# CAA-NMC-2-panels.net
KiCad netlist of a schematic drawn in EAGLE
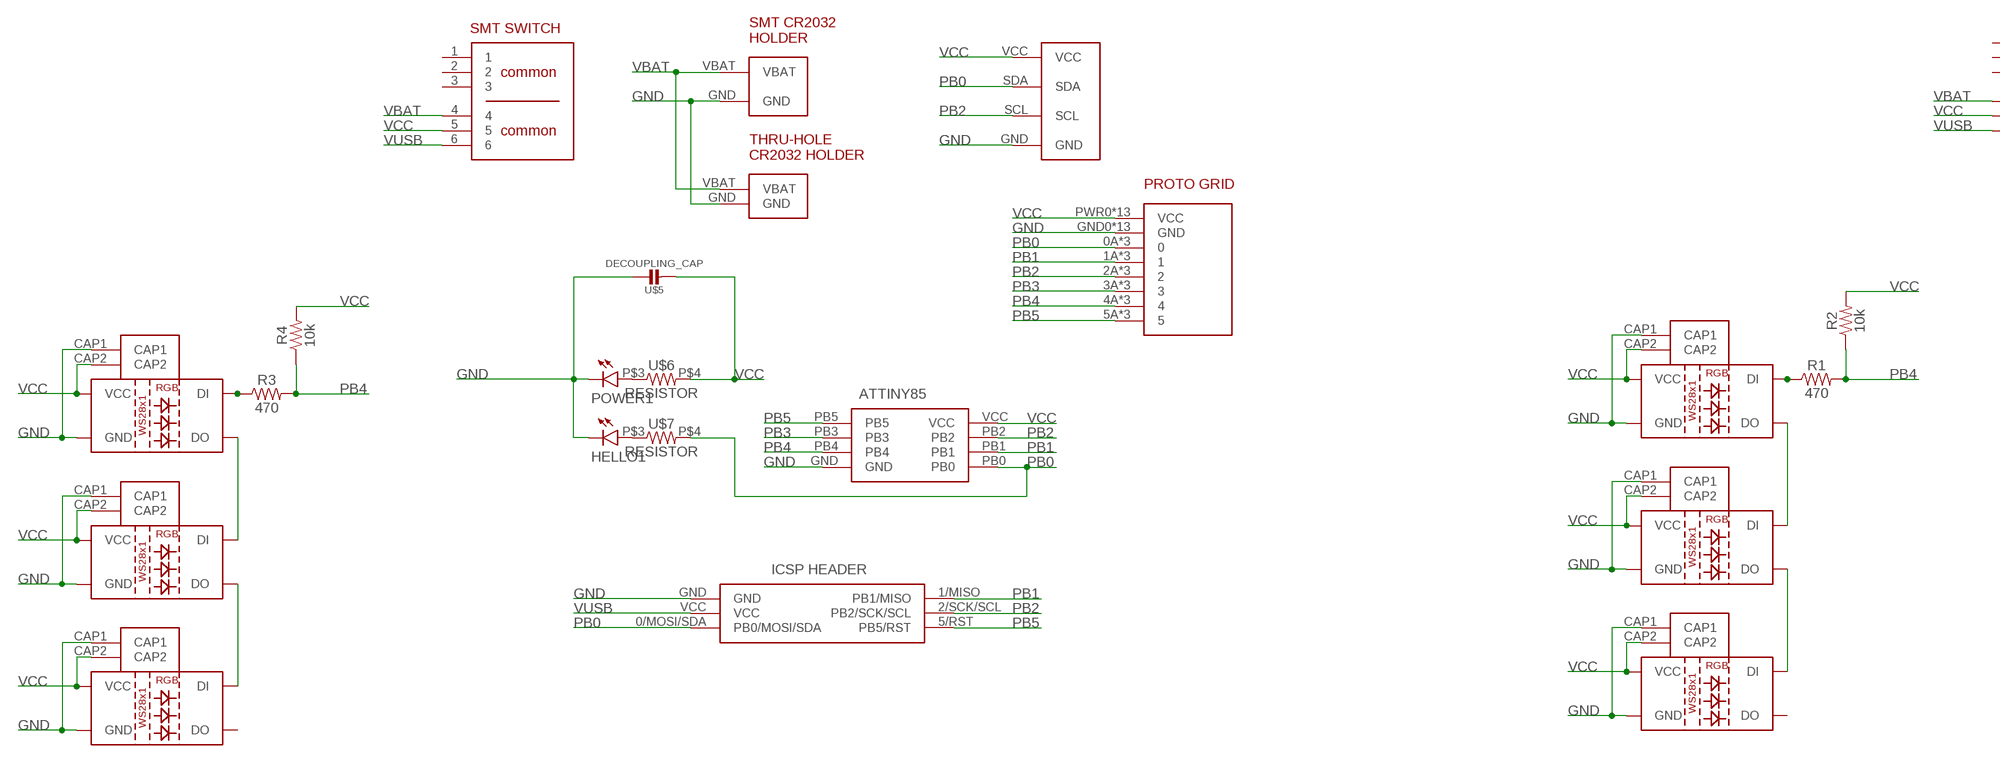
[diagram p0: schematic, sheet 1, part 1 of 2]
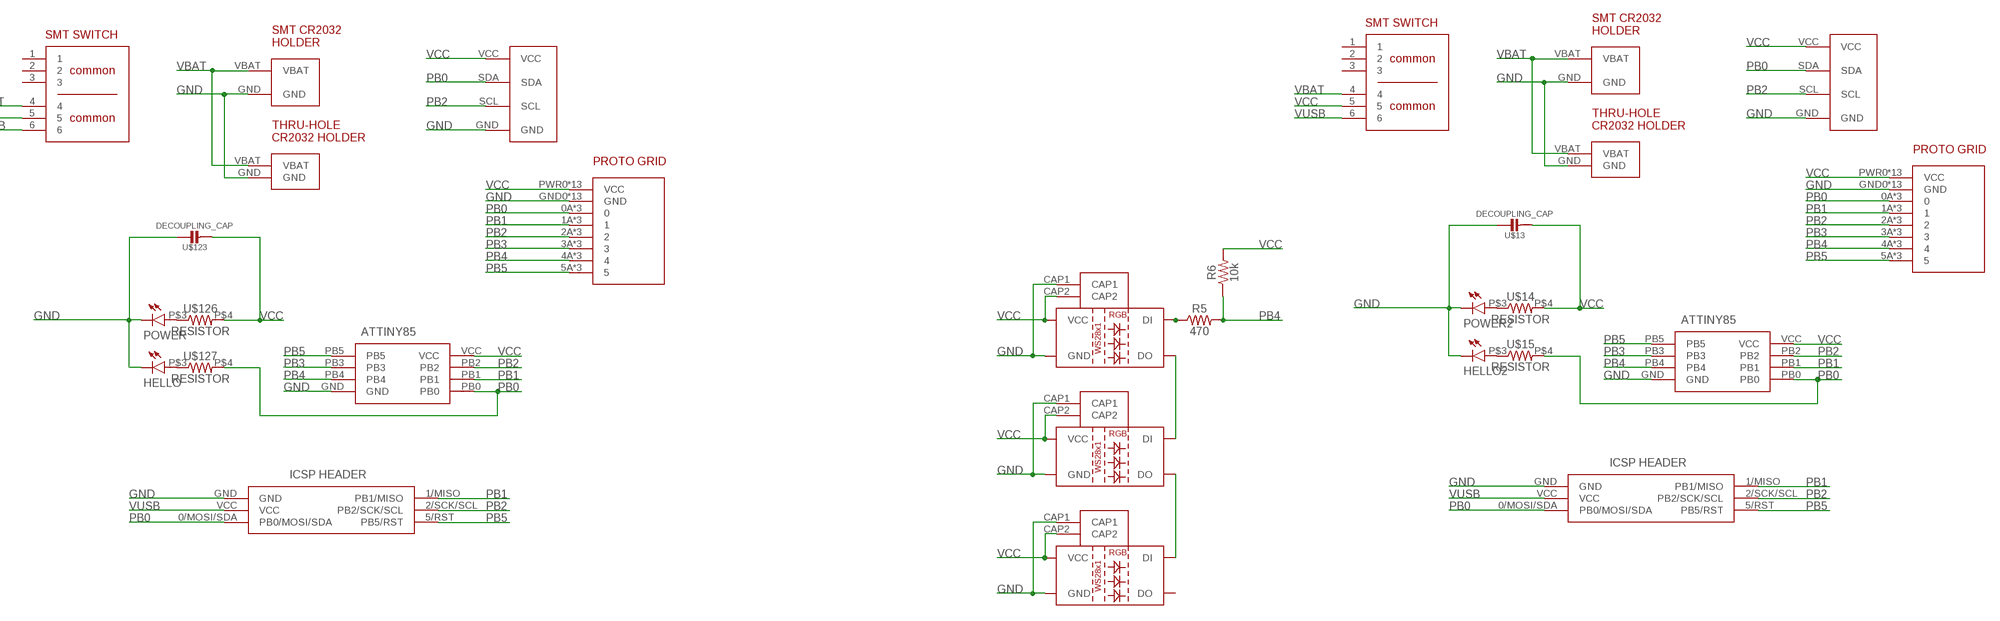
[diagram p1: schematic, sheet 1, part 2 of 2]

(export (version "E")
  (design (tool "Eeschema 10.0.6"))
  (components
    (comp (ref "D1")
      (value "WS2812B")
      (footprint "eagle-import:WS2812B")
      (libsource (lib "eagle-import") (part "WS2812B"))
    )
    (comp (ref "D2")
      (value "WS2812B")
      (footprint "eagle-import:WS2812B")
      (libsource (lib "eagle-import") (part "WS2812B"))
    )
    (comp (ref "D3")
      (value "WS2812B")
      (footprint "eagle-import:WS2812B")
      (libsource (lib "eagle-import") (part "WS2812B"))
    )
    (comp (ref "D4")
      (value "WS2812B")
      (footprint "eagle-import:WS2812B")
      (libsource (lib "eagle-import") (part "WS2812B"))
    )
    (comp (ref "D5")
      (value "WS2812B")
      (footprint "eagle-import:WS2812B")
      (libsource (lib "eagle-import") (part "WS2812B"))
    )
    (comp (ref "D6")
      (value "WS2812B")
      (footprint "eagle-import:WS2812B")
      (libsource (lib "eagle-import") (part "WS2812B"))
    )
    (comp (ref "D7")
      (value "WS2812B")
      (footprint "eagle-import:WS2812B")
      (libsource (lib "eagle-import") (part "WS2812B"))
    )
    (comp (ref "D8")
      (value "WS2812B")
      (footprint "eagle-import:WS2812B")
      (libsource (lib "eagle-import") (part "WS2812B"))
    )
    (comp (ref "D9")
      (value "WS2812B")
      (footprint "eagle-import:WS2812B")
      (libsource (lib "eagle-import") (part "WS2812B"))
    )
    (comp (ref "HELLO")
      (value "LED3MM")
      (footprint "eagle-import:LED3MM")
      (libsource (lib "eagle-import") (part "LED3MM"))
    )
    (comp (ref "HELLO1")
      (value "LED3MM")
      (footprint "eagle-import:LED3MM")
      (libsource (lib "eagle-import") (part "LED3MM"))
    )
    (comp (ref "HELLO2")
      (value "LED3MM")
      (footprint "eagle-import:LED3MM")
      (libsource (lib "eagle-import") (part "LED3MM"))
    )
    (comp (ref "IC1")
      (value "ATTINY85-20SU")
      (footprint "eagle-import:SOT127P798X216-8N")
      (fields (field (name "RS_PART_NUMBER") "1331674"))
      (libsource (lib "eagle-import") (part "ATTINY85-20SU"))
    )
    (comp (ref "IC2")
      (value "ATTINY85-20SU")
      (footprint "eagle-import:SOT127P798X216-8N")
      (fields (field (name "RS_PART_NUMBER") "1331674"))
      (libsource (lib "eagle-import") (part "ATTINY85-20SU"))
    )
    (comp (ref "IC3")
      (value "ATTINY85-20SU")
      (footprint "eagle-import:SOT127P798X216-8N")
      (fields (field (name "RS_PART_NUMBER") "1331674"))
      (libsource (lib "eagle-import") (part "ATTINY85-20SU"))
    )
    (comp (ref "J1")
      (value "M20-9980346")
      (footprint "eagle-import:HDRV6W64P254_2X3_762X508X868P")
      (fields (field (name "RS_PART_NUMBER") "7457046P"))
      (libsource (lib "eagle-import") (part "M20-9980346"))
    )
    (comp (ref "J2")
      (value "M20-9980346")
      (footprint "eagle-import:HDRV6W64P254_2X3_762X508X868P")
      (fields (field (name "RS_PART_NUMBER") "7457046P"))
      (libsource (lib "eagle-import") (part "M20-9980346"))
    )
    (comp (ref "J3")
      (value "M20-9980346")
      (footprint "eagle-import:HDRV6W64P254_2X3_762X508X868P")
      (fields (field (name "RS_PART_NUMBER") "7457046P"))
      (libsource (lib "eagle-import") (part "M20-9980346"))
    )
    (comp (ref "POWER")
      (value "LED3MM")
      (footprint "eagle-import:LED3MM")
      (libsource (lib "eagle-import") (part "LED3MM"))
    )
    (comp (ref "POWER1")
      (value "LED3MM")
      (footprint "eagle-import:LED3MM")
      (libsource (lib "eagle-import") (part "LED3MM"))
    )
    (comp (ref "POWER2")
      (value "LED3MM")
      (footprint "eagle-import:LED3MM")
      (libsource (lib "eagle-import") (part "LED3MM"))
    )
    (comp (ref "R1")
      (value "470")
      (footprint "eagle-import:0603")
      (libsource (lib "eagle-import") (part "470OHM-0603-1/10W-1%"))
    )
    (comp (ref "R2")
      (value "10k")
      (footprint "eagle-import:0603")
      (libsource (lib "eagle-import") (part "10KOHM-0603-1/10W-1%"))
    )
    (comp (ref "R3")
      (value "470")
      (footprint "eagle-import:0603")
      (libsource (lib "eagle-import") (part "470OHM-0603-1/10W-1%"))
    )
    (comp (ref "R4")
      (value "10k")
      (footprint "eagle-import:0603")
      (libsource (lib "eagle-import") (part "10KOHM-0603-1/10W-1%"))
    )
    (comp (ref "R5")
      (value "470")
      (footprint "eagle-import:0603")
      (libsource (lib "eagle-import") (part "470OHM-0603-1/10W-1%"))
    )
    (comp (ref "R6")
      (value "10k")
      (footprint "eagle-import:0603")
      (libsource (lib "eagle-import") (part "10KOHM-0603-1/10W-1%"))
    )
    (comp (ref "U$1")
      (value "PROTO")
      (footprint "eagle-import:PROTO")
      (libsource (lib "eagle-import") (part "PROTO"))
    )
    (comp (ref "U$2")
      (value "SMT-BATTERY-HOLDER")
      (footprint "eagle-import:SMT-CR-HOLDER")
      (libsource (lib "eagle-import") (part "SMT-BATTERY-HOLDER"))
    )
    (comp (ref "U$3")
      (value "THRU-CR-HOLDER")
      (footprint "eagle-import:THRU-CR-HOLDER")
      (libsource (lib "eagle-import") (part "THRU-CR-HOLDER"))
    )
    (comp (ref "U$4")
      (value "I2C-PADS")
      (footprint "eagle-import:I2C-PADS")
      (libsource (lib "eagle-import") (part "I2C-PADS"))
    )
    (comp (ref "U$5")
      (value "DECOUPLING_CAP")
      (footprint "eagle-import:DECOUPLING_CAP")
      (libsource (lib "eagle-import") (part "DECOUPLING_CAP"))
    )
    (comp (ref "U$6")
      (value "RESISTOR")
      (footprint "eagle-import:AXIAL-0.3")
      (libsource (lib "eagle-import") (part "RESISTOR"))
    )
    (comp (ref "U$7")
      (value "RESISTOR")
      (footprint "eagle-import:AXIAL-0.3")
      (libsource (lib "eagle-import") (part "RESISTOR"))
    )
    (comp (ref "U$8")
      (value "SMT-SWITCH")
      (footprint "eagle-import:SMT-SWITCH")
      (libsource (lib "eagle-import") (part "SMT-SWITCH"))
    )
    (comp (ref "U$9")
      (value "PROTO")
      (footprint "eagle-import:PROTO")
      (libsource (lib "eagle-import") (part "PROTO"))
    )
    (comp (ref "U$10")
      (value "SMT-BATTERY-HOLDER")
      (footprint "eagle-import:SMT-CR-HOLDER")
      (libsource (lib "eagle-import") (part "SMT-BATTERY-HOLDER"))
    )
    (comp (ref "U$11")
      (value "THRU-CR-HOLDER")
      (footprint "eagle-import:THRU-CR-HOLDER")
      (libsource (lib "eagle-import") (part "THRU-CR-HOLDER"))
    )
    (comp (ref "U$12")
      (value "I2C-PADS")
      (footprint "eagle-import:I2C-PADS")
      (libsource (lib "eagle-import") (part "I2C-PADS"))
    )
    (comp (ref "U$13")
      (value "DECOUPLING_CAP")
      (footprint "eagle-import:DECOUPLING_CAP")
      (libsource (lib "eagle-import") (part "DECOUPLING_CAP"))
    )
    (comp (ref "U$14")
      (value "RESISTOR")
      (footprint "eagle-import:AXIAL-0.3")
      (libsource (lib "eagle-import") (part "RESISTOR"))
    )
    (comp (ref "U$15")
      (value "RESISTOR")
      (footprint "eagle-import:AXIAL-0.3")
      (libsource (lib "eagle-import") (part "RESISTOR"))
    )
    (comp (ref "U$16")
      (value "SMT-SWITCH")
      (footprint "eagle-import:SMT-SWITCH")
      (libsource (lib "eagle-import") (part "SMT-SWITCH"))
    )
    (comp (ref "U$17")
      (value "PROTO")
      (footprint "eagle-import:PROTO")
      (libsource (lib "eagle-import") (part "PROTO"))
    )
    (comp (ref "U$18")
      (value "SMT-BATTERY-HOLDER")
      (footprint "eagle-import:SMT-CR-HOLDER")
      (libsource (lib "eagle-import") (part "SMT-BATTERY-HOLDER"))
    )
    (comp (ref "U$19")
      (value "THRU-CR-HOLDER")
      (footprint "eagle-import:THRU-CR-HOLDER")
      (libsource (lib "eagle-import") (part "THRU-CR-HOLDER"))
    )
    (comp (ref "U$20")
      (value "I2C-PADS")
      (footprint "eagle-import:I2C-PADS")
      (libsource (lib "eagle-import") (part "I2C-PADS"))
    )
    (comp (ref "U$123")
      (value "DECOUPLING_CAP")
      (footprint "eagle-import:DECOUPLING_CAP")
      (libsource (lib "eagle-import") (part "DECOUPLING_CAP"))
    )
    (comp (ref "U$126")
      (value "RESISTOR")
      (footprint "eagle-import:AXIAL-0.3")
      (libsource (lib "eagle-import") (part "RESISTOR"))
    )
    (comp (ref "U$127")
      (value "RESISTOR")
      (footprint "eagle-import:AXIAL-0.3")
      (libsource (lib "eagle-import") (part "RESISTOR"))
    )
    (comp (ref "U$145")
      (value "SMT-SWITCH")
      (footprint "eagle-import:SMT-SWITCH")
      (libsource (lib "eagle-import") (part "SMT-SWITCH"))
    )
  )
  (nets
    (net (code "1") (name "/GND") (class "Default")
      (node (ref "D1") (pin "CAP1") (pinfunction "CAP1_CAP1") (pintype "bidirectional"))
      (node (ref "D1") (pin "GND") (pinfunction "GND_GND") (pintype "bidirectional"))
      (node (ref "D2") (pin "CAP1") (pinfunction "CAP1_CAP1") (pintype "bidirectional"))
      (node (ref "D2") (pin "GND") (pinfunction "GND_GND") (pintype "bidirectional"))
      (node (ref "D3") (pin "CAP1") (pinfunction "CAP1_CAP1") (pintype "bidirectional"))
      (node (ref "D3") (pin "GND") (pinfunction "GND_GND") (pintype "bidirectional"))
      (node (ref "D4") (pin "CAP1") (pinfunction "CAP1_CAP1") (pintype "bidirectional"))
      (node (ref "D4") (pin "GND") (pinfunction "GND_GND") (pintype "bidirectional"))
      (node (ref "D5") (pin "CAP1") (pinfunction "CAP1_CAP1") (pintype "bidirectional"))
      (node (ref "D5") (pin "GND") (pinfunction "GND_GND") (pintype "bidirectional"))
      (node (ref "D6") (pin "CAP1") (pinfunction "CAP1_CAP1") (pintype "bidirectional"))
      (node (ref "D6") (pin "GND") (pinfunction "GND_GND") (pintype "bidirectional"))
      (node (ref "D7") (pin "CAP1") (pinfunction "CAP1_CAP1") (pintype "bidirectional"))
      (node (ref "D7") (pin "GND") (pinfunction "GND_GND") (pintype "bidirectional"))
      (node (ref "D8") (pin "CAP1") (pinfunction "CAP1_CAP1") (pintype "bidirectional"))
      (node (ref "D8") (pin "GND") (pinfunction "GND_GND") (pintype "bidirectional"))
      (node (ref "D9") (pin "CAP1") (pinfunction "CAP1_CAP1") (pintype "bidirectional"))
      (node (ref "D9") (pin "GND") (pinfunction "GND_GND") (pintype "bidirectional"))
      (node (ref "HELLO") (pin "NEG") (pinfunction "NEG_NEG") (pintype "passive"))
      (node (ref "HELLO1") (pin "NEG") (pinfunction "NEG_NEG") (pintype "passive"))
      (node (ref "HELLO2") (pin "NEG") (pinfunction "NEG_NEG") (pintype "passive"))
      (node (ref "IC1") (pin "GND") (pinfunction "GND_GND") (pintype "bidirectional"))
      (node (ref "IC2") (pin "GND") (pinfunction "GND_GND") (pintype "bidirectional"))
      (node (ref "IC3") (pin "GND") (pinfunction "GND_GND") (pintype "bidirectional"))
      (node (ref "J1") (pin "GND") (pinfunction "GND_GND") (pintype "bidirectional"))
      (node (ref "J2") (pin "GND") (pinfunction "GND_GND") (pintype "bidirectional"))
      (node (ref "J3") (pin "GND") (pinfunction "GND_GND") (pintype "bidirectional"))
      (node (ref "POWER") (pin "NEG") (pinfunction "NEG_NEG") (pintype "passive"))
      (node (ref "POWER1") (pin "NEG") (pinfunction "NEG_NEG") (pintype "passive"))
      (node (ref "POWER2") (pin "NEG") (pinfunction "NEG_NEG") (pintype "passive"))
      (node (ref "U$1") (pin "GND0") (pinfunction "GND_GND0") (pintype "bidirectional"))
      (node (ref "U$1") (pin "GND1") (pinfunction "GND_GND1") (pintype "bidirectional"))
      (node (ref "U$1") (pin "GND10") (pinfunction "GND_GND10") (pintype "bidirectional"))
      (node (ref "U$1") (pin "GND11") (pinfunction "GND_GND11") (pintype "bidirectional"))
      (node (ref "U$1") (pin "GND12") (pinfunction "GND_GND12") (pintype "bidirectional"))
      (node (ref "U$1") (pin "GND2") (pinfunction "GND_GND2") (pintype "bidirectional"))
      (node (ref "U$1") (pin "GND3") (pinfunction "GND_GND3") (pintype "bidirectional"))
      (node (ref "U$1") (pin "GND4") (pinfunction "GND_GND4") (pintype "bidirectional"))
      (node (ref "U$1") (pin "GND5") (pinfunction "GND_GND5") (pintype "bidirectional"))
      (node (ref "U$1") (pin "GND6") (pinfunction "GND_GND6") (pintype "bidirectional"))
      (node (ref "U$1") (pin "GND7") (pinfunction "GND_GND7") (pintype "bidirectional"))
      (node (ref "U$1") (pin "GND8") (pinfunction "GND_GND8") (pintype "bidirectional"))
      (node (ref "U$1") (pin "GND9") (pinfunction "GND_GND9") (pintype "bidirectional"))
      (node (ref "U$10") (pin "GND") (pinfunction "GND_GND") (pintype "bidirectional"))
      (node (ref "U$11") (pin "GND") (pinfunction "GND_GND") (pintype "bidirectional"))
      (node (ref "U$12") (pin "GND") (pinfunction "GND_GND") (pintype "bidirectional"))
      (node (ref "U$123") (pin "P$1") (pinfunction "1_P$1") (pintype "passive"))
      (node (ref "U$13") (pin "P$1") (pinfunction "1_P$1") (pintype "passive"))
      (node (ref "U$17") (pin "GND0") (pinfunction "GND_GND0") (pintype "bidirectional"))
      (node (ref "U$17") (pin "GND1") (pinfunction "GND_GND1") (pintype "bidirectional"))
      (node (ref "U$17") (pin "GND10") (pinfunction "GND_GND10") (pintype "bidirectional"))
      (node (ref "U$17") (pin "GND11") (pinfunction "GND_GND11") (pintype "bidirectional"))
      (node (ref "U$17") (pin "GND12") (pinfunction "GND_GND12") (pintype "bidirectional"))
      (node (ref "U$17") (pin "GND2") (pinfunction "GND_GND2") (pintype "bidirectional"))
      (node (ref "U$17") (pin "GND3") (pinfunction "GND_GND3") (pintype "bidirectional"))
      (node (ref "U$17") (pin "GND4") (pinfunction "GND_GND4") (pintype "bidirectional"))
      (node (ref "U$17") (pin "GND5") (pinfunction "GND_GND5") (pintype "bidirectional"))
      (node (ref "U$17") (pin "GND6") (pinfunction "GND_GND6") (pintype "bidirectional"))
      (node (ref "U$17") (pin "GND7") (pinfunction "GND_GND7") (pintype "bidirectional"))
      (node (ref "U$17") (pin "GND8") (pinfunction "GND_GND8") (pintype "bidirectional"))
      (node (ref "U$17") (pin "GND9") (pinfunction "GND_GND9") (pintype "bidirectional"))
      (node (ref "U$18") (pin "GND") (pinfunction "GND_GND") (pintype "bidirectional"))
      (node (ref "U$19") (pin "GND") (pinfunction "GND_GND") (pintype "bidirectional"))
      (node (ref "U$2") (pin "GND") (pinfunction "GND_GND") (pintype "bidirectional"))
      (node (ref "U$20") (pin "GND") (pinfunction "GND_GND") (pintype "bidirectional"))
      (node (ref "U$3") (pin "GND") (pinfunction "GND_GND") (pintype "bidirectional"))
      (node (ref "U$4") (pin "GND") (pinfunction "GND_GND") (pintype "bidirectional"))
      (node (ref "U$5") (pin "P$1") (pinfunction "1_P$1") (pintype "passive"))
      (node (ref "U$9") (pin "GND0") (pinfunction "GND_GND0") (pintype "bidirectional"))
      (node (ref "U$9") (pin "GND1") (pinfunction "GND_GND1") (pintype "bidirectional"))
      (node (ref "U$9") (pin "GND10") (pinfunction "GND_GND10") (pintype "bidirectional"))
      (node (ref "U$9") (pin "GND11") (pinfunction "GND_GND11") (pintype "bidirectional"))
      (node (ref "U$9") (pin "GND12") (pinfunction "GND_GND12") (pintype "bidirectional"))
      (node (ref "U$9") (pin "GND2") (pinfunction "GND_GND2") (pintype "bidirectional"))
      (node (ref "U$9") (pin "GND3") (pinfunction "GND_GND3") (pintype "bidirectional"))
      (node (ref "U$9") (pin "GND4") (pinfunction "GND_GND4") (pintype "bidirectional"))
      (node (ref "U$9") (pin "GND5") (pinfunction "GND_GND5") (pintype "bidirectional"))
      (node (ref "U$9") (pin "GND6") (pinfunction "GND_GND6") (pintype "bidirectional"))
      (node (ref "U$9") (pin "GND7") (pinfunction "GND_GND7") (pintype "bidirectional"))
      (node (ref "U$9") (pin "GND8") (pinfunction "GND_GND8") (pintype "bidirectional"))
      (node (ref "U$9") (pin "GND9") (pinfunction "GND_GND9") (pintype "bidirectional"))
    )
    (net (code "2") (name "/PB0") (class "Default")
      (node (ref "IC1") (pin "PB0") (pinfunction "PB0_PB0") (pintype "bidirectional"))
      (node (ref "IC2") (pin "PB0") (pinfunction "PB0_PB0") (pintype "bidirectional"))
      (node (ref "IC3") (pin "PB0") (pinfunction "PB0_PB0") (pintype "bidirectional"))
      (node (ref "J1") (pin "0/MOSI/SDA") (pinfunction "PB0/MOSI/SDA_0/MOSI/SDA") (pintype "bidirectional"))
      (node (ref "J2") (pin "0/MOSI/SDA") (pinfunction "PB0/MOSI/SDA_0/MOSI/SDA") (pintype "bidirectional"))
      (node (ref "J3") (pin "0/MOSI/SDA") (pinfunction "PB0/MOSI/SDA_0/MOSI/SDA") (pintype "bidirectional"))
      (node (ref "U$1") (pin "0A") (pinfunction "0_0A") (pintype "bidirectional"))
      (node (ref "U$1") (pin "0B") (pinfunction "0_0B") (pintype "bidirectional"))
      (node (ref "U$1") (pin "0C") (pinfunction "0_0C") (pintype "bidirectional"))
      (node (ref "U$12") (pin "SDA") (pinfunction "SDA_SDA") (pintype "bidirectional"))
      (node (ref "U$127") (pin "P$4") (pinfunction "2_P$4") (pintype "passive"))
      (node (ref "U$15") (pin "P$4") (pinfunction "2_P$4") (pintype "passive"))
      (node (ref "U$17") (pin "0A") (pinfunction "0_0A") (pintype "bidirectional"))
      (node (ref "U$17") (pin "0B") (pinfunction "0_0B") (pintype "bidirectional"))
      (node (ref "U$17") (pin "0C") (pinfunction "0_0C") (pintype "bidirectional"))
      (node (ref "U$20") (pin "SDA") (pinfunction "SDA_SDA") (pintype "bidirectional"))
      (node (ref "U$4") (pin "SDA") (pinfunction "SDA_SDA") (pintype "bidirectional"))
      (node (ref "U$7") (pin "P$4") (pinfunction "2_P$4") (pintype "passive"))
      (node (ref "U$9") (pin "0A") (pinfunction "0_0A") (pintype "bidirectional"))
      (node (ref "U$9") (pin "0B") (pinfunction "0_0B") (pintype "bidirectional"))
      (node (ref "U$9") (pin "0C") (pinfunction "0_0C") (pintype "bidirectional"))
    )
    (net (code "3") (name "/PB1") (class "Default")
      (node (ref "IC1") (pin "PB1") (pinfunction "PB1_PB1") (pintype "bidirectional"))
      (node (ref "IC2") (pin "PB1") (pinfunction "PB1_PB1") (pintype "bidirectional"))
      (node (ref "IC3") (pin "PB1") (pinfunction "PB1_PB1") (pintype "bidirectional"))
      (node (ref "J1") (pin "1/MISO") (pinfunction "PB1/MISO_1/MISO") (pintype "bidirectional"))
      (node (ref "J2") (pin "1/MISO") (pinfunction "PB1/MISO_1/MISO") (pintype "bidirectional"))
      (node (ref "J3") (pin "1/MISO") (pinfunction "PB1/MISO_1/MISO") (pintype "bidirectional"))
      (node (ref "U$1") (pin "1A") (pinfunction "1_1A") (pintype "bidirectional"))
      (node (ref "U$1") (pin "1B") (pinfunction "1_1B") (pintype "bidirectional"))
      (node (ref "U$1") (pin "1C") (pinfunction "1_1C") (pintype "bidirectional"))
      (node (ref "U$17") (pin "1A") (pinfunction "1_1A") (pintype "bidirectional"))
      (node (ref "U$17") (pin "1B") (pinfunction "1_1B") (pintype "bidirectional"))
      (node (ref "U$17") (pin "1C") (pinfunction "1_1C") (pintype "bidirectional"))
      (node (ref "U$9") (pin "1A") (pinfunction "1_1A") (pintype "bidirectional"))
      (node (ref "U$9") (pin "1B") (pinfunction "1_1B") (pintype "bidirectional"))
      (node (ref "U$9") (pin "1C") (pinfunction "1_1C") (pintype "bidirectional"))
    )
    (net (code "4") (name "/PB2") (class "Default")
      (node (ref "IC1") (pin "PB2") (pinfunction "PB2_PB2") (pintype "bidirectional"))
      (node (ref "IC2") (pin "PB2") (pinfunction "PB2_PB2") (pintype "bidirectional"))
      (node (ref "IC3") (pin "PB2") (pinfunction "PB2_PB2") (pintype "bidirectional"))
      (node (ref "J1") (pin "2/SCK/SCL") (pinfunction "PB2/SCK/SCL_2/SCK/SCL") (pintype "bidirectional"))
      (node (ref "J2") (pin "2/SCK/SCL") (pinfunction "PB2/SCK/SCL_2/SCK/SCL") (pintype "bidirectional"))
      (node (ref "J3") (pin "2/SCK/SCL") (pinfunction "PB2/SCK/SCL_2/SCK/SCL") (pintype "bidirectional"))
      (node (ref "U$1") (pin "2A") (pinfunction "2_2A") (pintype "bidirectional"))
      (node (ref "U$1") (pin "2B") (pinfunction "2_2B") (pintype "bidirectional"))
      (node (ref "U$1") (pin "2C") (pinfunction "2_2C") (pintype "bidirectional"))
      (node (ref "U$12") (pin "SCL") (pinfunction "SCL_SCL") (pintype "bidirectional"))
      (node (ref "U$17") (pin "2A") (pinfunction "2_2A") (pintype "bidirectional"))
      (node (ref "U$17") (pin "2B") (pinfunction "2_2B") (pintype "bidirectional"))
      (node (ref "U$17") (pin "2C") (pinfunction "2_2C") (pintype "bidirectional"))
      (node (ref "U$20") (pin "SCL") (pinfunction "SCL_SCL") (pintype "bidirectional"))
      (node (ref "U$4") (pin "SCL") (pinfunction "SCL_SCL") (pintype "bidirectional"))
      (node (ref "U$9") (pin "2A") (pinfunction "2_2A") (pintype "bidirectional"))
      (node (ref "U$9") (pin "2B") (pinfunction "2_2B") (pintype "bidirectional"))
      (node (ref "U$9") (pin "2C") (pinfunction "2_2C") (pintype "bidirectional"))
    )
    (net (code "5") (name "/PB3") (class "Default")
      (node (ref "IC1") (pin "PB3") (pinfunction "PB3_PB3") (pintype "bidirectional"))
      (node (ref "IC2") (pin "PB3") (pinfunction "PB3_PB3") (pintype "bidirectional"))
      (node (ref "IC3") (pin "PB3") (pinfunction "PB3_PB3") (pintype "bidirectional"))
      (node (ref "U$1") (pin "3A") (pinfunction "3_3A") (pintype "bidirectional"))
      (node (ref "U$1") (pin "3B") (pinfunction "3_3B") (pintype "bidirectional"))
      (node (ref "U$1") (pin "3C") (pinfunction "3_3C") (pintype "bidirectional"))
      (node (ref "U$17") (pin "3A") (pinfunction "3_3A") (pintype "bidirectional"))
      (node (ref "U$17") (pin "3B") (pinfunction "3_3B") (pintype "bidirectional"))
      (node (ref "U$17") (pin "3C") (pinfunction "3_3C") (pintype "bidirectional"))
      (node (ref "U$9") (pin "3A") (pinfunction "3_3A") (pintype "bidirectional"))
      (node (ref "U$9") (pin "3B") (pinfunction "3_3B") (pintype "bidirectional"))
      (node (ref "U$9") (pin "3C") (pinfunction "3_3C") (pintype "bidirectional"))
    )
    (net (code "6") (name "/PB4") (class "Default")
      (node (ref "IC1") (pin "PB4") (pinfunction "PB4_PB4") (pintype "bidirectional"))
      (node (ref "IC2") (pin "PB4") (pinfunction "PB4_PB4") (pintype "bidirectional"))
      (node (ref "IC3") (pin "PB4") (pinfunction "PB4_PB4") (pintype "bidirectional"))
      (node (ref "R1") (pin "2") (pinfunction "2_2") (pintype "passive"))
      (node (ref "R2") (pin "1") (pinfunction "1_1") (pintype "passive"))
      (node (ref "R3") (pin "2") (pinfunction "2_2") (pintype "passive"))
      (node (ref "R4") (pin "1") (pinfunction "1_1") (pintype "passive"))
      (node (ref "R5") (pin "2") (pinfunction "2_2") (pintype "passive"))
      (node (ref "R6") (pin "1") (pinfunction "1_1") (pintype "passive"))
      (node (ref "U$1") (pin "4A") (pinfunction "4_4A") (pintype "bidirectional"))
      (node (ref "U$1") (pin "4B") (pinfunction "4_4B") (pintype "bidirectional"))
      (node (ref "U$1") (pin "4C") (pinfunction "4_4C") (pintype "bidirectional"))
      (node (ref "U$17") (pin "4A") (pinfunction "4_4A") (pintype "bidirectional"))
      (node (ref "U$17") (pin "4B") (pinfunction "4_4B") (pintype "bidirectional"))
      (node (ref "U$17") (pin "4C") (pinfunction "4_4C") (pintype "bidirectional"))
      (node (ref "U$9") (pin "4A") (pinfunction "4_4A") (pintype "bidirectional"))
      (node (ref "U$9") (pin "4B") (pinfunction "4_4B") (pintype "bidirectional"))
      (node (ref "U$9") (pin "4C") (pinfunction "4_4C") (pintype "bidirectional"))
    )
    (net (code "7") (name "/PB5") (class "Default")
      (node (ref "IC1") (pin "PB5") (pinfunction "PB5_PB5") (pintype "bidirectional"))
      (node (ref "IC2") (pin "PB5") (pinfunction "PB5_PB5") (pintype "bidirectional"))
      (node (ref "IC3") (pin "PB5") (pinfunction "PB5_PB5") (pintype "bidirectional"))
      (node (ref "J1") (pin "5/RST") (pinfunction "PB5/RST_5/RST") (pintype "bidirectional"))
      (node (ref "J2") (pin "5/RST") (pinfunction "PB5/RST_5/RST") (pintype "bidirectional"))
      (node (ref "J3") (pin "5/RST") (pinfunction "PB5/RST_5/RST") (pintype "bidirectional"))
      (node (ref "U$1") (pin "5A") (pinfunction "5_5A") (pintype "bidirectional"))
      (node (ref "U$1") (pin "5B") (pinfunction "5_5B") (pintype "bidirectional"))
      (node (ref "U$1") (pin "5C") (pinfunction "5_5C") (pintype "bidirectional"))
      (node (ref "U$17") (pin "5A") (pinfunction "5_5A") (pintype "bidirectional"))
      (node (ref "U$17") (pin "5B") (pinfunction "5_5B") (pintype "bidirectional"))
      (node (ref "U$17") (pin "5C") (pinfunction "5_5C") (pintype "bidirectional"))
      (node (ref "U$9") (pin "5A") (pinfunction "5_5A") (pintype "bidirectional"))
      (node (ref "U$9") (pin "5B") (pinfunction "5_5B") (pintype "bidirectional"))
      (node (ref "U$9") (pin "5C") (pinfunction "5_5C") (pintype "bidirectional"))
    )
    (net (code "8") (name "/VBAT") (class "Default")
      (node (ref "U$10") (pin "VBAT") (pinfunction "VBAT_VBAT") (pintype "bidirectional"))
      (node (ref "U$11") (pin "VBAT") (pinfunction "VBAT_VBAT") (pintype "bidirectional"))
      (node (ref "U$145") (pin "4") (pinfunction "4_4") (pintype "bidirectional"))
      (node (ref "U$16") (pin "4") (pinfunction "4_4") (pintype "bidirectional"))
      (node (ref "U$18") (pin "VBAT") (pinfunction "VBAT_VBAT") (pintype "bidirectional"))
      (node (ref "U$19") (pin "VBAT") (pinfunction "VBAT_VBAT") (pintype "bidirectional"))
      (node (ref "U$2") (pin "VBAT") (pinfunction "VBAT_VBAT") (pintype "bidirectional"))
      (node (ref "U$3") (pin "VBAT") (pinfunction "VBAT_VBAT") (pintype "bidirectional"))
      (node (ref "U$8") (pin "4") (pinfunction "4_4") (pintype "bidirectional"))
    )
    (net (code "9") (name "/VCC") (class "Default")
      (node (ref "D1") (pin "CAP2") (pinfunction "CAP2_CAP2") (pintype "bidirectional"))
      (node (ref "D1") (pin "VCC") (pinfunction "VCC_VCC") (pintype "bidirectional"))
      (node (ref "D2") (pin "CAP2") (pinfunction "CAP2_CAP2") (pintype "bidirectional"))
      (node (ref "D2") (pin "VCC") (pinfunction "VCC_VCC") (pintype "bidirectional"))
      (node (ref "D3") (pin "CAP2") (pinfunction "CAP2_CAP2") (pintype "bidirectional"))
      (node (ref "D3") (pin "VCC") (pinfunction "VCC_VCC") (pintype "bidirectional"))
      (node (ref "D4") (pin "CAP2") (pinfunction "CAP2_CAP2") (pintype "bidirectional"))
      (node (ref "D4") (pin "VCC") (pinfunction "VCC_VCC") (pintype "bidirectional"))
      (node (ref "D5") (pin "CAP2") (pinfunction "CAP2_CAP2") (pintype "bidirectional"))
      (node (ref "D5") (pin "VCC") (pinfunction "VCC_VCC") (pintype "bidirectional"))
      (node (ref "D6") (pin "CAP2") (pinfunction "CAP2_CAP2") (pintype "bidirectional"))
      (node (ref "D6") (pin "VCC") (pinfunction "VCC_VCC") (pintype "bidirectional"))
      (node (ref "D7") (pin "CAP2") (pinfunction "CAP2_CAP2") (pintype "bidirectional"))
      (node (ref "D7") (pin "VCC") (pinfunction "VCC_VCC") (pintype "bidirectional"))
      (node (ref "D8") (pin "CAP2") (pinfunction "CAP2_CAP2") (pintype "bidirectional"))
      (node (ref "D8") (pin "VCC") (pinfunction "VCC_VCC") (pintype "bidirectional"))
      (node (ref "D9") (pin "CAP2") (pinfunction "CAP2_CAP2") (pintype "bidirectional"))
      (node (ref "D9") (pin "VCC") (pinfunction "VCC_VCC") (pintype "bidirectional"))
      (node (ref "IC1") (pin "VCC") (pinfunction "VCC_VCC") (pintype "bidirectional"))
      (node (ref "IC2") (pin "VCC") (pinfunction "VCC_VCC") (pintype "bidirectional"))
      (node (ref "IC3") (pin "VCC") (pinfunction "VCC_VCC") (pintype "bidirectional"))
      (node (ref "R2") (pin "2") (pinfunction "2_2") (pintype "passive"))
      (node (ref "R4") (pin "2") (pinfunction "2_2") (pintype "passive"))
      (node (ref "R6") (pin "2") (pinfunction "2_2") (pintype "passive"))
      (node (ref "U$1") (pin "PWR0") (pinfunction "VCC_PWR0") (pintype "bidirectional"))
      (node (ref "U$1") (pin "PWR1") (pinfunction "VCC_PWR1") (pintype "bidirectional"))
      (node (ref "U$1") (pin "PWR10") (pinfunction "VCC_PWR10") (pintype "bidirectional"))
      (node (ref "U$1") (pin "PWR11") (pinfunction "VCC_PWR11") (pintype "bidirectional"))
      (node (ref "U$1") (pin "PWR12") (pinfunction "VCC_PWR12") (pintype "bidirectional"))
      (node (ref "U$1") (pin "PWR2") (pinfunction "VCC_PWR2") (pintype "bidirectional"))
      (node (ref "U$1") (pin "PWR3") (pinfunction "VCC_PWR3") (pintype "bidirectional"))
      (node (ref "U$1") (pin "PWR4") (pinfunction "VCC_PWR4") (pintype "bidirectional"))
      (node (ref "U$1") (pin "PWR5") (pinfunction "VCC_PWR5") (pintype "bidirectional"))
      (node (ref "U$1") (pin "PWR6") (pinfunction "VCC_PWR6") (pintype "bidirectional"))
      (node (ref "U$1") (pin "PWR7") (pinfunction "VCC_PWR7") (pintype "bidirectional"))
      (node (ref "U$1") (pin "PWR8") (pinfunction "VCC_PWR8") (pintype "bidirectional"))
      (node (ref "U$1") (pin "PWR9") (pinfunction "VCC_PWR9") (pintype "bidirectional"))
      (node (ref "U$12") (pin "VCC") (pinfunction "VCC_VCC") (pintype "bidirectional"))
      (node (ref "U$123") (pin "P$2") (pinfunction "2_P$2") (pintype "passive"))
      (node (ref "U$126") (pin "P$4") (pinfunction "2_P$4") (pintype "passive"))
      (node (ref "U$13") (pin "P$2") (pinfunction "2_P$2") (pintype "passive"))
      (node (ref "U$14") (pin "P$4") (pinfunction "2_P$4") (pintype "passive"))
      (node (ref "U$145") (pin "5") (pinfunction "5_5") (pintype "bidirectional"))
      (node (ref "U$16") (pin "5") (pinfunction "5_5") (pintype "bidirectional"))
      (node (ref "U$17") (pin "PWR0") (pinfunction "VCC_PWR0") (pintype "bidirectional"))
      (node (ref "U$17") (pin "PWR1") (pinfunction "VCC_PWR1") (pintype "bidirectional"))
      (node (ref "U$17") (pin "PWR10") (pinfunction "VCC_PWR10") (pintype "bidirectional"))
      (node (ref "U$17") (pin "PWR11") (pinfunction "VCC_PWR11") (pintype "bidirectional"))
      (node (ref "U$17") (pin "PWR12") (pinfunction "VCC_PWR12") (pintype "bidirectional"))
      (node (ref "U$17") (pin "PWR2") (pinfunction "VCC_PWR2") (pintype "bidirectional"))
      (node (ref "U$17") (pin "PWR3") (pinfunction "VCC_PWR3") (pintype "bidirectional"))
      (node (ref "U$17") (pin "PWR4") (pinfunction "VCC_PWR4") (pintype "bidirectional"))
      (node (ref "U$17") (pin "PWR5") (pinfunction "VCC_PWR5") (pintype "bidirectional"))
      (node (ref "U$17") (pin "PWR6") (pinfunction "VCC_PWR6") (pintype "bidirectional"))
      (node (ref "U$17") (pin "PWR7") (pinfunction "VCC_PWR7") (pintype "bidirectional"))
      (node (ref "U$17") (pin "PWR8") (pinfunction "VCC_PWR8") (pintype "bidirectional"))
      (node (ref "U$17") (pin "PWR9") (pinfunction "VCC_PWR9") (pintype "bidirectional"))
      (node (ref "U$20") (pin "VCC") (pinfunction "VCC_VCC") (pintype "bidirectional"))
      (node (ref "U$4") (pin "VCC") (pinfunction "VCC_VCC") (pintype "bidirectional"))
      (node (ref "U$5") (pin "P$2") (pinfunction "2_P$2") (pintype "passive"))
      (node (ref "U$6") (pin "P$4") (pinfunction "2_P$4") (pintype "passive"))
      (node (ref "U$8") (pin "5") (pinfunction "5_5") (pintype "bidirectional"))
      (node (ref "U$9") (pin "PWR0") (pinfunction "VCC_PWR0") (pintype "bidirectional"))
      (node (ref "U$9") (pin "PWR1") (pinfunction "VCC_PWR1") (pintype "bidirectional"))
      (node (ref "U$9") (pin "PWR10") (pinfunction "VCC_PWR10") (pintype "bidirectional"))
      (node (ref "U$9") (pin "PWR11") (pinfunction "VCC_PWR11") (pintype "bidirectional"))
      (node (ref "U$9") (pin "PWR12") (pinfunction "VCC_PWR12") (pintype "bidirectional"))
      (node (ref "U$9") (pin "PWR2") (pinfunction "VCC_PWR2") (pintype "bidirectional"))
      (node (ref "U$9") (pin "PWR3") (pinfunction "VCC_PWR3") (pintype "bidirectional"))
      (node (ref "U$9") (pin "PWR4") (pinfunction "VCC_PWR4") (pintype "bidirectional"))
      (node (ref "U$9") (pin "PWR5") (pinfunction "VCC_PWR5") (pintype "bidirectional"))
      (node (ref "U$9") (pin "PWR6") (pinfunction "VCC_PWR6") (pintype "bidirectional"))
      (node (ref "U$9") (pin "PWR7") (pinfunction "VCC_PWR7") (pintype "bidirectional"))
      (node (ref "U$9") (pin "PWR8") (pinfunction "VCC_PWR8") (pintype "bidirectional"))
      (node (ref "U$9") (pin "PWR9") (pinfunction "VCC_PWR9") (pintype "bidirectional"))
    )
    (net (code "10") (name "/VUSB") (class "Default")
      (node (ref "J1") (pin "VCC") (pinfunction "VCC_VCC") (pintype "bidirectional"))
      (node (ref "J2") (pin "VCC") (pinfunction "VCC_VCC") (pintype "bidirectional"))
      (node (ref "J3") (pin "VCC") (pinfunction "VCC_VCC") (pintype "bidirectional"))
      (node (ref "U$145") (pin "6") (pinfunction "6_6") (pintype "bidirectional"))
      (node (ref "U$16") (pin "6") (pinfunction "6_6") (pintype "bidirectional"))
      (node (ref "U$8") (pin "6") (pinfunction "6_6") (pintype "bidirectional"))
    )
    (net (code "11") (name "Net-(D1-PadDI)") (class "Default")
      (node (ref "D1") (pin "DI") (pinfunction "DI_DI") (pintype "bidirectional"))
      (node (ref "R1") (pin "1") (pinfunction "1_1") (pintype "passive"))
    )
    (net (code "12") (name "Net-(D1-PadDO)") (class "Default")
      (node (ref "D1") (pin "DO") (pinfunction "DO_DO") (pintype "bidirectional"))
      (node (ref "D2") (pin "DI") (pinfunction "DI_DI") (pintype "bidirectional"))
    )
    (net (code "13") (name "Net-(D2-PadDO)") (class "Default")
      (node (ref "D2") (pin "DO") (pinfunction "DO_DO") (pintype "bidirectional"))
      (node (ref "D3") (pin "DI") (pinfunction "DI_DI") (pintype "bidirectional"))
    )
    (net (code "14") (name "Net-(D4-PadDI)") (class "Default")
      (node (ref "D4") (pin "DI") (pinfunction "DI_DI") (pintype "bidirectional"))
      (node (ref "R3") (pin "1") (pinfunction "1_1") (pintype "passive"))
    )
    (net (code "15") (name "Net-(D4-PadDO)") (class "Default")
      (node (ref "D4") (pin "DO") (pinfunction "DO_DO") (pintype "bidirectional"))
      (node (ref "D5") (pin "DI") (pinfunction "DI_DI") (pintype "bidirectional"))
    )
    (net (code "16") (name "Net-(D5-PadDO)") (class "Default")
      (node (ref "D5") (pin "DO") (pinfunction "DO_DO") (pintype "bidirectional"))
      (node (ref "D6") (pin "DI") (pinfunction "DI_DI") (pintype "bidirectional"))
    )
    (net (code "17") (name "Net-(D7-PadDI)") (class "Default")
      (node (ref "D7") (pin "DI") (pinfunction "DI_DI") (pintype "bidirectional"))
      (node (ref "R5") (pin "1") (pinfunction "1_1") (pintype "passive"))
    )
    (net (code "18") (name "Net-(D7-PadDO)") (class "Default")
      (node (ref "D7") (pin "DO") (pinfunction "DO_DO") (pintype "bidirectional"))
      (node (ref "D8") (pin "DI") (pinfunction "DI_DI") (pintype "bidirectional"))
    )
    (net (code "19") (name "Net-(D8-PadDO)") (class "Default")
      (node (ref "D8") (pin "DO") (pinfunction "DO_DO") (pintype "bidirectional"))
      (node (ref "D9") (pin "DI") (pinfunction "DI_DI") (pintype "bidirectional"))
    )
    (net (code "20") (name "Net-(U$6-1)") (class "Default")
      (node (ref "POWER1") (pin "POS") (pinfunction "POS_POS") (pintype "passive"))
      (node (ref "U$6") (pin "P$3") (pinfunction "1_P$3") (pintype "passive"))
    )
    (net (code "21") (name "Net-(U$7-1)") (class "Default")
      (node (ref "HELLO1") (pin "POS") (pinfunction "POS_POS") (pintype "passive"))
      (node (ref "U$7") (pin "P$3") (pinfunction "1_P$3") (pintype "passive"))
    )
    (net (code "22") (name "Net-(U$14-1)") (class "Default")
      (node (ref "POWER2") (pin "POS") (pinfunction "POS_POS") (pintype "passive"))
      (node (ref "U$14") (pin "P$3") (pinfunction "1_P$3") (pintype "passive"))
    )
    (net (code "23") (name "Net-(U$15-1)") (class "Default")
      (node (ref "HELLO2") (pin "POS") (pinfunction "POS_POS") (pintype "passive"))
      (node (ref "U$15") (pin "P$3") (pinfunction "1_P$3") (pintype "passive"))
    )
    (net (code "24") (name "Net-(U$126-1)") (class "Default")
      (node (ref "POWER") (pin "POS") (pinfunction "POS_POS") (pintype "passive"))
      (node (ref "U$126") (pin "P$3") (pinfunction "1_P$3") (pintype "passive"))
    )
    (net (code "25") (name "Net-(U$127-1)") (class "Default")
      (node (ref "HELLO") (pin "POS") (pinfunction "POS_POS") (pintype "passive"))
      (node (ref "U$127") (pin "P$3") (pinfunction "1_P$3") (pintype "passive"))
    )
    (net (code "26") (name "unconnected-(D3-PadDO)") (class "Default")
      (node (ref "D3") (pin "DO") (pinfunction "DO_DO") (pintype "bidirectional"))
    )
    (net (code "27") (name "unconnected-(D6-PadDO)") (class "Default")
      (node (ref "D6") (pin "DO") (pinfunction "DO_DO") (pintype "bidirectional"))
    )
    (net (code "28") (name "unconnected-(D9-PadDO)") (class "Default")
      (node (ref "D9") (pin "DO") (pinfunction "DO_DO") (pintype "bidirectional"))
    )
    (net (code "29") (name "unconnected-(U$8-Pad1)") (class "Default")
      (node (ref "U$8") (pin "1") (pinfunction "1_1") (pintype "bidirectional"))
    )
    (net (code "30") (name "unconnected-(U$8-Pad2)") (class "Default")
      (node (ref "U$8") (pin "2") (pinfunction "2_2") (pintype "bidirectional"))
    )
    (net (code "31") (name "unconnected-(U$8-Pad3)") (class "Default")
      (node (ref "U$8") (pin "3") (pinfunction "3_3") (pintype "bidirectional"))
    )
    (net (code "32") (name "unconnected-(U$16-Pad1)") (class "Default")
      (node (ref "U$16") (pin "1") (pinfunction "1_1") (pintype "bidirectional"))
    )
    (net (code "33") (name "unconnected-(U$16-Pad2)") (class "Default")
      (node (ref "U$16") (pin "2") (pinfunction "2_2") (pintype "bidirectional"))
    )
    (net (code "34") (name "unconnected-(U$16-Pad3)") (class "Default")
      (node (ref "U$16") (pin "3") (pinfunction "3_3") (pintype "bidirectional"))
    )
    (net (code "35") (name "unconnected-(U$145-Pad1)") (class "Default")
      (node (ref "U$145") (pin "1") (pinfunction "1_1") (pintype "bidirectional"))
    )
    (net (code "36") (name "unconnected-(U$145-Pad2)") (class "Default")
      (node (ref "U$145") (pin "2") (pinfunction "2_2") (pintype "bidirectional"))
    )
    (net (code "37") (name "unconnected-(U$145-Pad3)") (class "Default")
      (node (ref "U$145") (pin "3") (pinfunction "3_3") (pintype "bidirectional"))
    )
  )
)
